# BoardForIV.net
KiCad netlist of a schematic drawn in Altium Designer
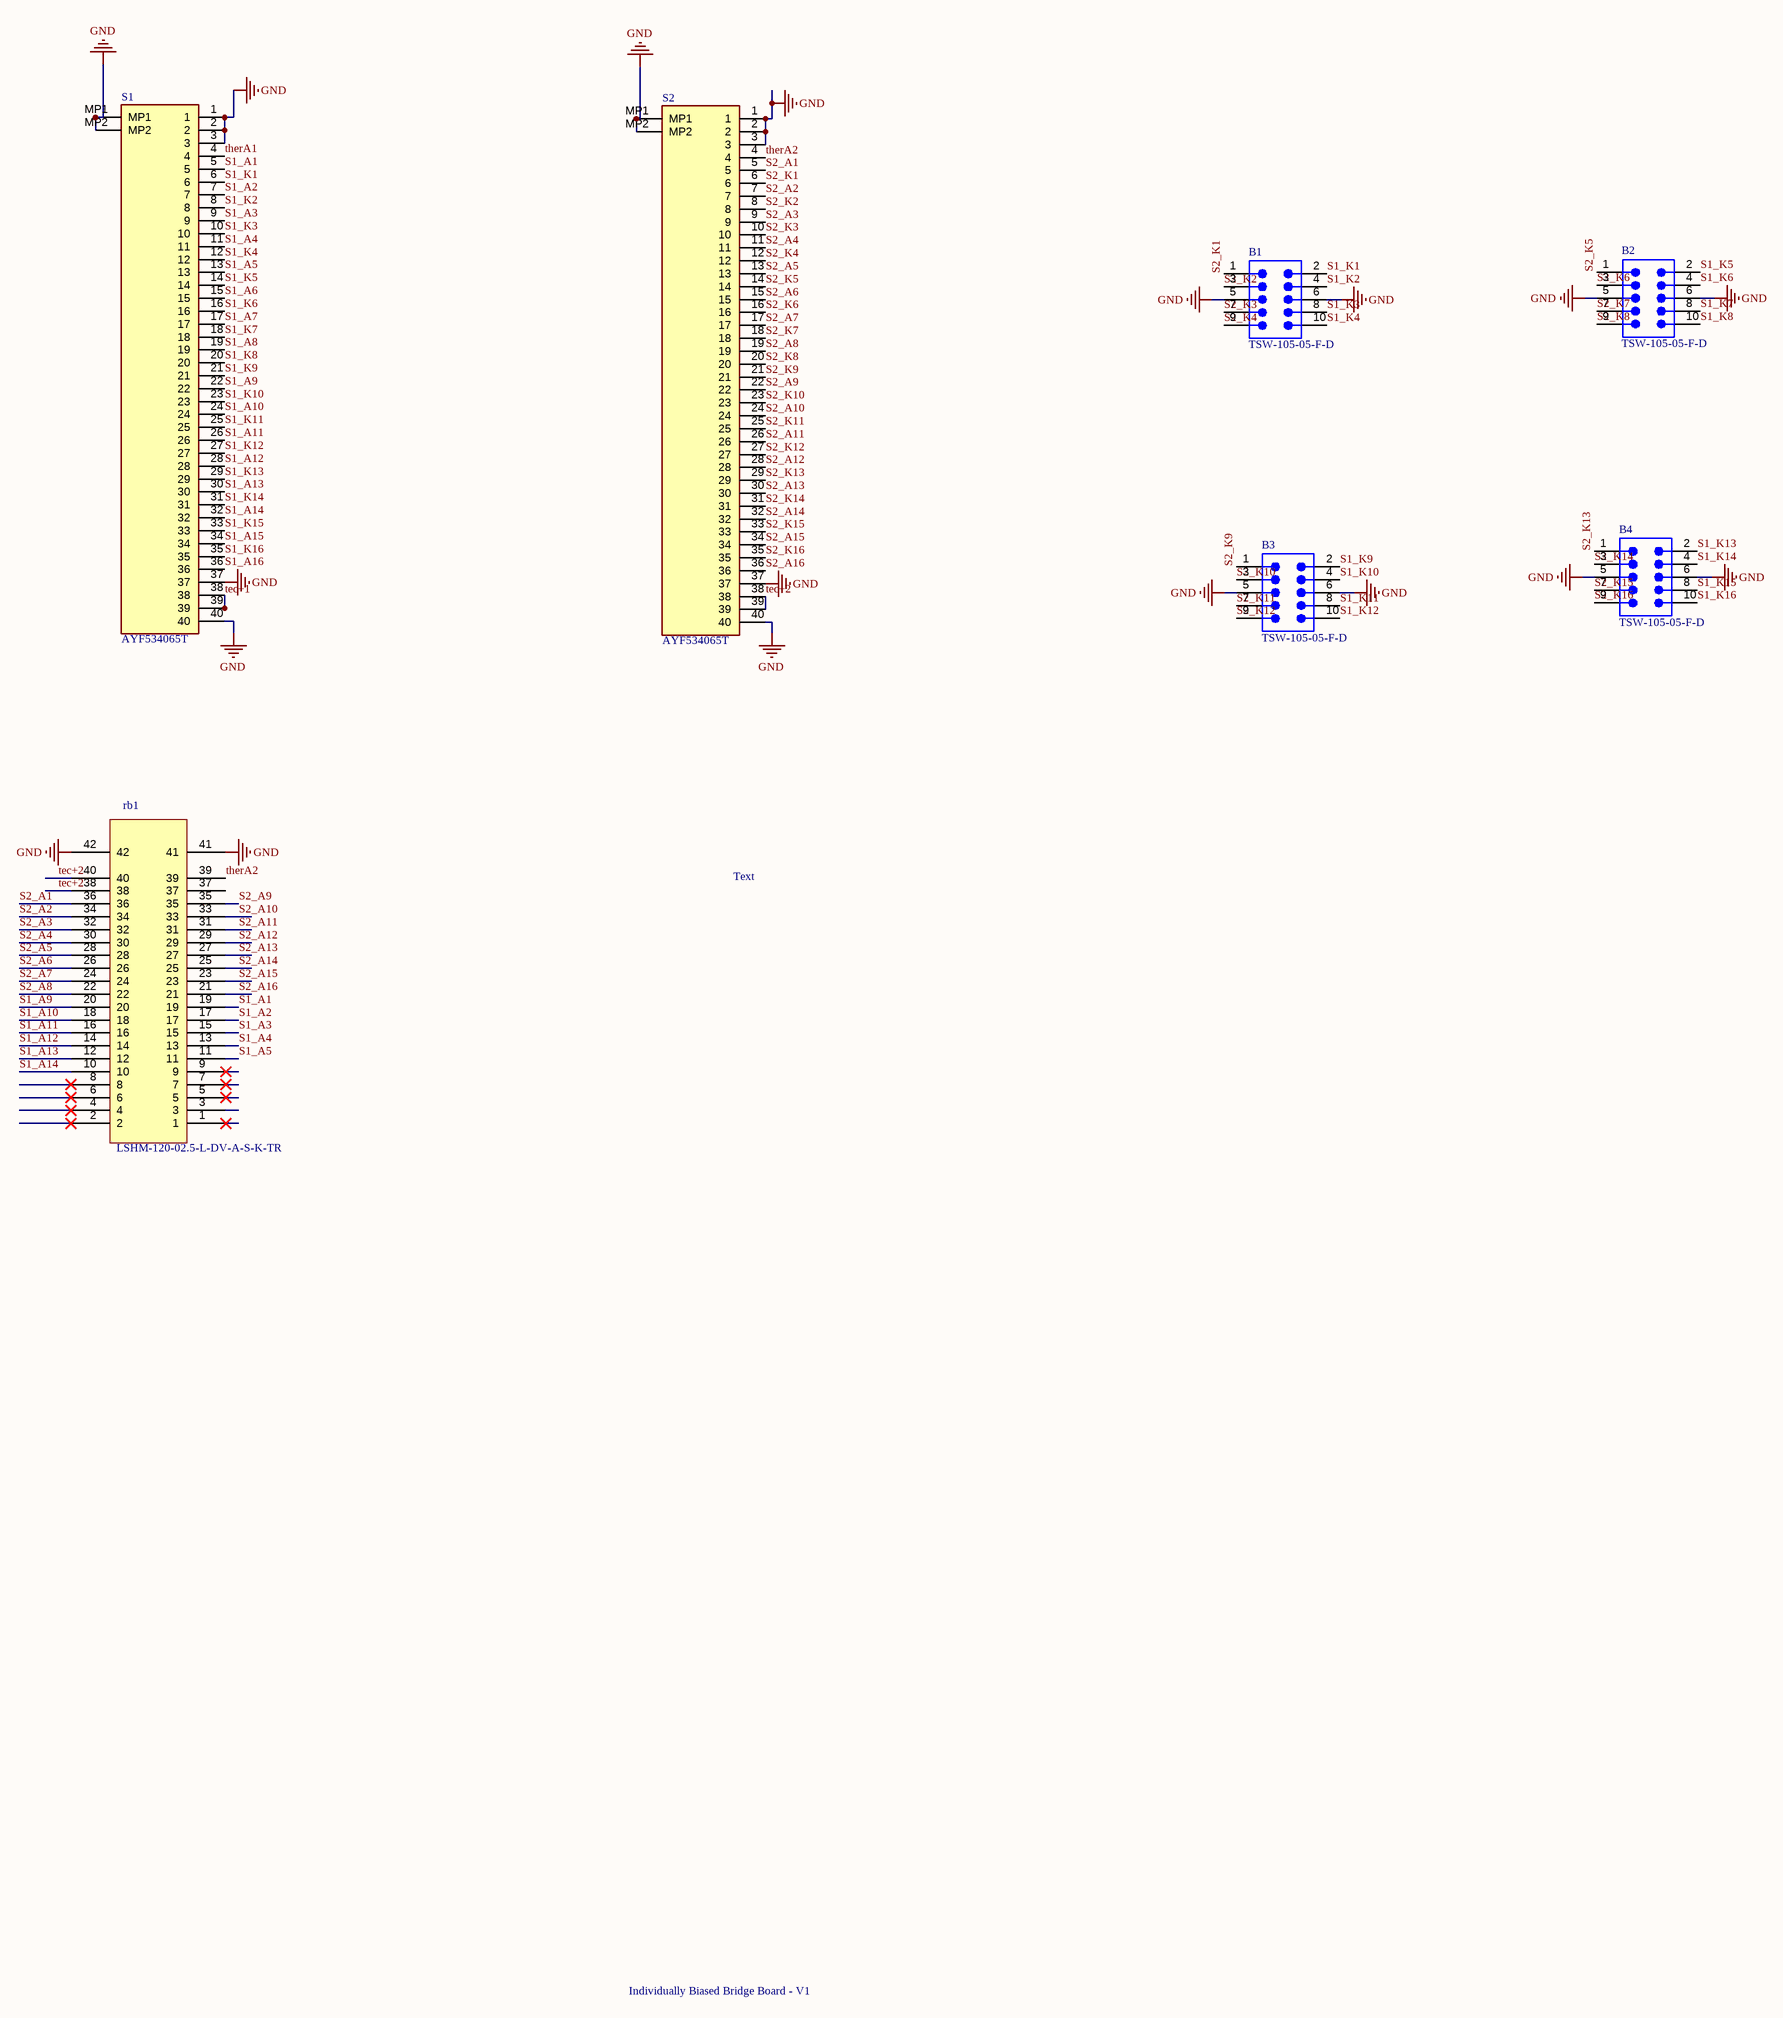
[diagram p0: BoardForIV.SchDoc]

(export (version "E")
  (design (tool "Eeschema 10.0.6"))
  (components
    (comp (ref "B1")
      (value "TSW-105-05-F-D")
      (footprint "SMTC-TSW-105-05-X-D")
      (description "0.025\" SQ Post Header, Through-hole, Vertical, -55 to 125 degC, 2.54 mm Pitch, 10-Pin, Male, RoHS")
      (fields (field (name "MANUFACTURER") "Samtec"))
      (libsource (lib "Altium Content Vault") (part "SMTC-TSW-105-X-X-D-X"))
    )
    (comp (ref "B2")
      (value "TSW-105-05-F-D")
      (footprint "SMTC-TSW-105-05-X-D")
      (description "0.025\" SQ Post Header, Through-hole, Vertical, -55 to 125 degC, 2.54 mm Pitch, 10-Pin, Male, RoHS")
      (fields (field (name "MANUFACTURER") "Samtec"))
      (libsource (lib "Altium Content Vault") (part "SMTC-TSW-105-X-X-D-X"))
    )
    (comp (ref "B3")
      (value "TSW-105-05-F-D")
      (footprint "SMTC-TSW-105-05-X-D")
      (description "0.025\" SQ Post Header, Through-hole, Vertical, -55 to 125 degC, 2.54 mm Pitch, 10-Pin, Male, RoHS")
      (fields (field (name "MANUFACTURER") "Samtec"))
      (libsource (lib "Altium Content Vault") (part "SMTC-TSW-105-X-X-D-X"))
    )
    (comp (ref "B4")
      (value "TSW-105-05-F-D")
      (footprint "SMTC-TSW-105-05-X-D")
      (description "0.025\" SQ Post Header, Through-hole, Vertical, -55 to 125 degC, 2.54 mm Pitch, 10-Pin, Male, RoHS")
      (fields (field (name "MANUFACTURER") "Samtec"))
      (libsource (lib "Altium Content Vault") (part "SMTC-TSW-105-X-X-D-X"))
    )
    (comp (ref "rb1")
      (value "LSHM-120-02.5-L-DV-A-S-K-TR")
      (footprint "SAMTEC_LSHM-120-02.5-L-DV-A-S-TR")
      (description "razor beam 40")
      (libsource (lib "JPL") (part "LSHM-120-02.5-L-DV-A-S-K-TR"))
    )
    (comp (ref "S1")
      (value "AYF534065T")
      (footprint "AYF534065T:AYF534065T")
      (libsource (lib "SiPM") (part "AYF534035"))
    )
    (comp (ref "S2")
      (value "AYF534065T")
      (footprint "AYF534065T:AYF534065T")
      (libsource (lib "Miscellaneous Devices") (part "AYF534035"))
    )
  )
  (nets
    (net (code "1") (name "/S1_A1") (class "Default")
      (node (ref "S1") (pin "5") (pinfunction "5_5") (pintype "passive"))
      (node (ref "rb1") (pin "19") (pinfunction "19_19") (pintype "passive"))
    )
    (net (code "2") (name "/S1_A2") (class "Default")
      (node (ref "S1") (pin "7") (pinfunction "7_7") (pintype "passive"))
      (node (ref "rb1") (pin "17") (pinfunction "17_17") (pintype "passive"))
    )
    (net (code "3") (name "/S1_A3") (class "Default")
      (node (ref "S1") (pin "9") (pinfunction "9_9") (pintype "passive"))
      (node (ref "rb1") (pin "15") (pinfunction "15_15") (pintype "passive"))
    )
    (net (code "4") (name "/S1_A4") (class "Default")
      (node (ref "S1") (pin "11") (pinfunction "11_11") (pintype "passive"))
      (node (ref "rb1") (pin "13") (pinfunction "13_13") (pintype "passive"))
    )
    (net (code "5") (name "/S1_A5") (class "Default")
      (node (ref "S1") (pin "13") (pinfunction "13_13") (pintype "passive"))
      (node (ref "rb1") (pin "11") (pinfunction "11_11") (pintype "passive"))
    )
    (net (code "6") (name "/S1_A6") (class "Default")
      (node (ref "S1") (pin "15") (pinfunction "15_15") (pintype "passive"))
    )
    (net (code "7") (name "/S1_A7") (class "Default")
      (node (ref "S1") (pin "17") (pinfunction "17_17") (pintype "passive"))
    )
    (net (code "8") (name "/S1_A8") (class "Default")
      (node (ref "S1") (pin "19") (pinfunction "19_19") (pintype "passive"))
    )
    (net (code "9") (name "/S1_A9") (class "Default")
      (node (ref "S1") (pin "22") (pinfunction "22_22") (pintype "passive"))
      (node (ref "rb1") (pin "20") (pinfunction "20_20") (pintype "passive"))
    )
    (net (code "10") (name "/S1_A10") (class "Default")
      (node (ref "S1") (pin "24") (pinfunction "24_24") (pintype "passive"))
      (node (ref "rb1") (pin "18") (pinfunction "18_18") (pintype "passive"))
    )
    (net (code "11") (name "/S1_A11") (class "Default")
      (node (ref "S1") (pin "26") (pinfunction "26_26") (pintype "passive"))
      (node (ref "rb1") (pin "16") (pinfunction "16_16") (pintype "passive"))
    )
    (net (code "12") (name "/S1_A12") (class "Default")
      (node (ref "S1") (pin "28") (pinfunction "28_28") (pintype "passive"))
      (node (ref "rb1") (pin "14") (pinfunction "14_14") (pintype "passive"))
    )
    (net (code "13") (name "/S1_A13") (class "Default")
      (node (ref "S1") (pin "30") (pinfunction "30_30") (pintype "passive"))
      (node (ref "rb1") (pin "12") (pinfunction "12_12") (pintype "passive"))
    )
    (net (code "14") (name "/S1_A14") (class "Default")
      (node (ref "S1") (pin "32") (pinfunction "32_32") (pintype "passive"))
      (node (ref "rb1") (pin "10") (pinfunction "10_10") (pintype "passive"))
    )
    (net (code "15") (name "/S1_A15") (class "Default")
      (node (ref "S1") (pin "34") (pinfunction "34_34") (pintype "passive"))
    )
    (net (code "16") (name "/S1_A16") (class "Default")
      (node (ref "S1") (pin "36") (pinfunction "36_36") (pintype "passive"))
    )
    (net (code "17") (name "/S1_K1") (class "Default")
      (node (ref "B1") (pin "2") (pinfunction "2_2") (pintype "passive"))
      (node (ref "S1") (pin "6") (pinfunction "6_6") (pintype "passive"))
    )
    (net (code "18") (name "/S1_K2") (class "Default")
      (node (ref "B1") (pin "4") (pinfunction "4_4") (pintype "passive"))
      (node (ref "S1") (pin "8") (pinfunction "8_8") (pintype "passive"))
    )
    (net (code "19") (name "/S1_K3") (class "Default")
      (node (ref "B1") (pin "8") (pinfunction "8_8") (pintype "passive"))
      (node (ref "S1") (pin "10") (pinfunction "10_10") (pintype "passive"))
    )
    (net (code "20") (name "/S1_K4") (class "Default")
      (node (ref "B1") (pin "10") (pinfunction "10_10") (pintype "passive"))
      (node (ref "S1") (pin "12") (pinfunction "12_12") (pintype "passive"))
    )
    (net (code "21") (name "/S1_K5") (class "Default")
      (node (ref "B2") (pin "2") (pinfunction "2_2") (pintype "passive"))
      (node (ref "S1") (pin "14") (pinfunction "14_14") (pintype "passive"))
    )
    (net (code "22") (name "/S1_K6") (class "Default")
      (node (ref "B2") (pin "4") (pinfunction "4_4") (pintype "passive"))
      (node (ref "S1") (pin "16") (pinfunction "16_16") (pintype "passive"))
    )
    (net (code "23") (name "/S1_K7") (class "Default")
      (node (ref "B2") (pin "8") (pinfunction "8_8") (pintype "passive"))
      (node (ref "S1") (pin "18") (pinfunction "18_18") (pintype "passive"))
    )
    (net (code "24") (name "/S1_K8") (class "Default")
      (node (ref "B2") (pin "10") (pinfunction "10_10") (pintype "passive"))
      (node (ref "S1") (pin "20") (pinfunction "20_20") (pintype "passive"))
    )
    (net (code "25") (name "/S1_K9") (class "Default")
      (node (ref "B3") (pin "2") (pinfunction "2_2") (pintype "passive"))
      (node (ref "S1") (pin "21") (pinfunction "21_21") (pintype "passive"))
    )
    (net (code "26") (name "/S1_K10") (class "Default")
      (node (ref "B3") (pin "4") (pinfunction "4_4") (pintype "passive"))
      (node (ref "S1") (pin "23") (pinfunction "23_23") (pintype "passive"))
    )
    (net (code "27") (name "/S1_K11") (class "Default")
      (node (ref "B3") (pin "8") (pinfunction "8_8") (pintype "passive"))
      (node (ref "S1") (pin "25") (pinfunction "25_25") (pintype "passive"))
    )
    (net (code "28") (name "/S1_K12") (class "Default")
      (node (ref "B3") (pin "10") (pinfunction "10_10") (pintype "passive"))
      (node (ref "S1") (pin "27") (pinfunction "27_27") (pintype "passive"))
    )
    (net (code "29") (name "/S1_K13") (class "Default")
      (node (ref "B4") (pin "2") (pinfunction "2_2") (pintype "passive"))
      (node (ref "S1") (pin "29") (pinfunction "29_29") (pintype "passive"))
    )
    (net (code "30") (name "/S1_K14") (class "Default")
      (node (ref "B4") (pin "4") (pinfunction "4_4") (pintype "passive"))
      (node (ref "S1") (pin "31") (pinfunction "31_31") (pintype "passive"))
    )
    (net (code "31") (name "/S1_K15") (class "Default")
      (node (ref "B4") (pin "8") (pinfunction "8_8") (pintype "passive"))
      (node (ref "S1") (pin "33") (pinfunction "33_33") (pintype "passive"))
    )
    (net (code "32") (name "/S1_K16") (class "Default")
      (node (ref "B4") (pin "10") (pinfunction "10_10") (pintype "passive"))
      (node (ref "S1") (pin "35") (pinfunction "35_35") (pintype "passive"))
    )
    (net (code "33") (name "/S2_A1") (class "Default")
      (node (ref "S2") (pin "5") (pinfunction "5_5") (pintype "passive"))
      (node (ref "rb1") (pin "36") (pinfunction "36_36") (pintype "passive"))
    )
    (net (code "34") (name "/S2_A2") (class "Default")
      (node (ref "S2") (pin "7") (pinfunction "7_7") (pintype "passive"))
      (node (ref "rb1") (pin "34") (pinfunction "34_34") (pintype "passive"))
    )
    (net (code "35") (name "/S2_A3") (class "Default")
      (node (ref "S2") (pin "9") (pinfunction "9_9") (pintype "passive"))
      (node (ref "rb1") (pin "32") (pinfunction "32_32") (pintype "passive"))
    )
    (net (code "36") (name "/S2_A4") (class "Default")
      (node (ref "S2") (pin "11") (pinfunction "11_11") (pintype "passive"))
      (node (ref "rb1") (pin "30") (pinfunction "30_30") (pintype "passive"))
    )
    (net (code "37") (name "/S2_A5") (class "Default")
      (node (ref "S2") (pin "13") (pinfunction "13_13") (pintype "passive"))
      (node (ref "rb1") (pin "28") (pinfunction "28_28") (pintype "passive"))
    )
    (net (code "38") (name "/S2_A6") (class "Default")
      (node (ref "S2") (pin "15") (pinfunction "15_15") (pintype "passive"))
      (node (ref "rb1") (pin "26") (pinfunction "26_26") (pintype "passive"))
    )
    (net (code "39") (name "/S2_A7") (class "Default")
      (node (ref "S2") (pin "17") (pinfunction "17_17") (pintype "passive"))
      (node (ref "rb1") (pin "24") (pinfunction "24_24") (pintype "passive"))
    )
    (net (code "40") (name "/S2_A8") (class "Default")
      (node (ref "S2") (pin "19") (pinfunction "19_19") (pintype "passive"))
      (node (ref "rb1") (pin "22") (pinfunction "22_22") (pintype "passive"))
    )
    (net (code "41") (name "/S2_A9") (class "Default")
      (node (ref "S2") (pin "22") (pinfunction "22_22") (pintype "passive"))
      (node (ref "rb1") (pin "35") (pinfunction "35_35") (pintype "passive"))
    )
    (net (code "42") (name "/S2_A10") (class "Default")
      (node (ref "S2") (pin "24") (pinfunction "24_24") (pintype "passive"))
      (node (ref "rb1") (pin "33") (pinfunction "33_33") (pintype "passive"))
    )
    (net (code "43") (name "/S2_A11") (class "Default")
      (node (ref "S2") (pin "26") (pinfunction "26_26") (pintype "passive"))
      (node (ref "rb1") (pin "31") (pinfunction "31_31") (pintype "passive"))
    )
    (net (code "44") (name "/S2_A12") (class "Default")
      (node (ref "S2") (pin "28") (pinfunction "28_28") (pintype "passive"))
      (node (ref "rb1") (pin "29") (pinfunction "29_29") (pintype "passive"))
    )
    (net (code "45") (name "/S2_A13") (class "Default")
      (node (ref "S2") (pin "30") (pinfunction "30_30") (pintype "passive"))
      (node (ref "rb1") (pin "27") (pinfunction "27_27") (pintype "passive"))
    )
    (net (code "46") (name "/S2_A14") (class "Default")
      (node (ref "S2") (pin "32") (pinfunction "32_32") (pintype "passive"))
      (node (ref "rb1") (pin "25") (pinfunction "25_25") (pintype "passive"))
    )
    (net (code "47") (name "/S2_A15") (class "Default")
      (node (ref "S2") (pin "34") (pinfunction "34_34") (pintype "passive"))
      (node (ref "rb1") (pin "23") (pinfunction "23_23") (pintype "passive"))
    )
    (net (code "48") (name "/S2_A16") (class "Default")
      (node (ref "S2") (pin "36") (pinfunction "36_36") (pintype "passive"))
      (node (ref "rb1") (pin "21") (pinfunction "21_21") (pintype "passive"))
    )
    (net (code "49") (name "/S2_K1") (class "Default")
      (node (ref "B1") (pin "1") (pinfunction "1_1") (pintype "passive"))
      (node (ref "S2") (pin "6") (pinfunction "6_6") (pintype "passive"))
    )
    (net (code "50") (name "/S2_K2") (class "Default")
      (node (ref "B1") (pin "3") (pinfunction "3_3") (pintype "passive"))
      (node (ref "S2") (pin "8") (pinfunction "8_8") (pintype "passive"))
    )
    (net (code "51") (name "/S2_K3") (class "Default")
      (node (ref "B1") (pin "7") (pinfunction "7_7") (pintype "passive"))
      (node (ref "S2") (pin "10") (pinfunction "10_10") (pintype "passive"))
    )
    (net (code "52") (name "/S2_K4") (class "Default")
      (node (ref "B1") (pin "9") (pinfunction "9_9") (pintype "passive"))
      (node (ref "S2") (pin "12") (pinfunction "12_12") (pintype "passive"))
    )
    (net (code "53") (name "/S2_K5") (class "Default")
      (node (ref "B2") (pin "1") (pinfunction "1_1") (pintype "passive"))
      (node (ref "S2") (pin "14") (pinfunction "14_14") (pintype "passive"))
    )
    (net (code "54") (name "/S2_K6") (class "Default")
      (node (ref "B2") (pin "3") (pinfunction "3_3") (pintype "passive"))
      (node (ref "S2") (pin "16") (pinfunction "16_16") (pintype "passive"))
    )
    (net (code "55") (name "/S2_K7") (class "Default")
      (node (ref "B2") (pin "7") (pinfunction "7_7") (pintype "passive"))
      (node (ref "S2") (pin "18") (pinfunction "18_18") (pintype "passive"))
    )
    (net (code "56") (name "/S2_K8") (class "Default")
      (node (ref "B2") (pin "9") (pinfunction "9_9") (pintype "passive"))
      (node (ref "S2") (pin "20") (pinfunction "20_20") (pintype "passive"))
    )
    (net (code "57") (name "/S2_K9") (class "Default")
      (node (ref "B3") (pin "1") (pinfunction "1_1") (pintype "passive"))
      (node (ref "S2") (pin "21") (pinfunction "21_21") (pintype "passive"))
    )
    (net (code "58") (name "/S2_K10") (class "Default")
      (node (ref "B3") (pin "3") (pinfunction "3_3") (pintype "passive"))
      (node (ref "S2") (pin "23") (pinfunction "23_23") (pintype "passive"))
    )
    (net (code "59") (name "/S2_K11") (class "Default")
      (node (ref "B3") (pin "7") (pinfunction "7_7") (pintype "passive"))
      (node (ref "S2") (pin "25") (pinfunction "25_25") (pintype "passive"))
    )
    (net (code "60") (name "/S2_K12") (class "Default")
      (node (ref "B3") (pin "9") (pinfunction "9_9") (pintype "passive"))
      (node (ref "S2") (pin "27") (pinfunction "27_27") (pintype "passive"))
    )
    (net (code "61") (name "/S2_K13") (class "Default")
      (node (ref "B4") (pin "1") (pinfunction "1_1") (pintype "passive"))
      (node (ref "S2") (pin "29") (pinfunction "29_29") (pintype "passive"))
    )
    (net (code "62") (name "/S2_K14") (class "Default")
      (node (ref "B4") (pin "3") (pinfunction "3_3") (pintype "passive"))
      (node (ref "S2") (pin "31") (pinfunction "31_31") (pintype "passive"))
    )
    (net (code "63") (name "/S2_K15") (class "Default")
      (node (ref "B4") (pin "7") (pinfunction "7_7") (pintype "passive"))
      (node (ref "S2") (pin "33") (pinfunction "33_33") (pintype "passive"))
    )
    (net (code "64") (name "/S2_K16") (class "Default")
      (node (ref "B4") (pin "9") (pinfunction "9_9") (pintype "passive"))
      (node (ref "S2") (pin "35") (pinfunction "35_35") (pintype "passive"))
    )
    (net (code "65") (name "/tec+1") (class "Default")
      (node (ref "S1") (pin "38") (pinfunction "38_38") (pintype "passive"))
      (node (ref "S1") (pin "39") (pinfunction "39_39") (pintype "passive"))
    )
    (net (code "66") (name "/tec+2") (class "Default")
      (node (ref "S2") (pin "38") (pinfunction "38_38") (pintype "passive"))
      (node (ref "S2") (pin "39") (pinfunction "39_39") (pintype "passive"))
      (node (ref "rb1") (pin "38") (pinfunction "38_38") (pintype "passive"))
      (node (ref "rb1") (pin "40") (pinfunction "40_40") (pintype "passive"))
    )
    (net (code "67") (name "/therA1") (class "Default")
      (node (ref "S1") (pin "4") (pinfunction "4_4") (pintype "passive"))
    )
    (net (code "68") (name "/therA2") (class "Default")
      (node (ref "S2") (pin "4") (pinfunction "4_4") (pintype "passive"))
      (node (ref "rb1") (pin "39") (pinfunction "39_39") (pintype "passive"))
    )
    (net (code "69") (name "GND") (class "Default")
      (node (ref "B1") (pin "5") (pinfunction "5_5") (pintype "passive"))
      (node (ref "B1") (pin "6") (pinfunction "6_6") (pintype "passive"))
      (node (ref "B2") (pin "5") (pinfunction "5_5") (pintype "passive"))
      (node (ref "B2") (pin "6") (pinfunction "6_6") (pintype "passive"))
      (node (ref "B3") (pin "5") (pinfunction "5_5") (pintype "passive"))
      (node (ref "B3") (pin "6") (pinfunction "6_6") (pintype "passive"))
      (node (ref "B4") (pin "5") (pinfunction "5_5") (pintype "passive"))
      (node (ref "B4") (pin "6") (pinfunction "6_6") (pintype "passive"))
      (node (ref "S1") (pin "1") (pinfunction "1_1") (pintype "passive"))
      (node (ref "S1") (pin "2") (pinfunction "2_2") (pintype "passive"))
      (node (ref "S1") (pin "3") (pinfunction "3_3") (pintype "passive"))
      (node (ref "S1") (pin "37") (pinfunction "37_37") (pintype "passive"))
      (node (ref "S1") (pin "40") (pinfunction "40_40") (pintype "passive"))
      (node (ref "S1") (pin "MP1") (pinfunction "MP1_MP1") (pintype "passive"))
      (node (ref "S1") (pin "MP2") (pinfunction "MP2_MP2") (pintype "passive"))
      (node (ref "S2") (pin "1") (pinfunction "1_1") (pintype "passive"))
      (node (ref "S2") (pin "2") (pinfunction "2_2") (pintype "passive"))
      (node (ref "S2") (pin "3") (pinfunction "3_3") (pintype "passive"))
      (node (ref "S2") (pin "37") (pinfunction "37_37") (pintype "passive"))
      (node (ref "S2") (pin "40") (pinfunction "40_40") (pintype "passive"))
      (node (ref "S2") (pin "MP1") (pinfunction "MP1_MP1") (pintype "passive"))
      (node (ref "S2") (pin "MP2") (pinfunction "MP2_MP2") (pintype "passive"))
      (node (ref "rb1") (pin "41") (pinfunction "41_41") (pintype "passive"))
      (node (ref "rb1") (pin "42") (pinfunction "42_42") (pintype "passive"))
    )
    (net (code "70") (name "unconnected-(rb1-Pad1)") (class "Default")
      (node (ref "rb1") (pin "1") (pinfunction "1_1") (pintype "passive+no_connect"))
    )
    (net (code "71") (name "unconnected-(rb1-Pad2)") (class "Default")
      (node (ref "rb1") (pin "2") (pinfunction "2_2") (pintype "passive+no_connect"))
    )
    (net (code "72") (name "unconnected-(rb1-Pad3)") (class "Default")
      (node (ref "rb1") (pin "3") (pinfunction "3_3") (pintype "passive"))
    )
    (net (code "73") (name "unconnected-(rb1-Pad4)") (class "Default")
      (node (ref "rb1") (pin "4") (pinfunction "4_4") (pintype "passive+no_connect"))
    )
    (net (code "74") (name "unconnected-(rb1-Pad5)") (class "Default")
      (node (ref "rb1") (pin "5") (pinfunction "5_5") (pintype "passive+no_connect"))
    )
    (net (code "75") (name "unconnected-(rb1-Pad6)") (class "Default")
      (node (ref "rb1") (pin "6") (pinfunction "6_6") (pintype "passive+no_connect"))
    )
    (net (code "76") (name "unconnected-(rb1-Pad7)") (class "Default")
      (node (ref "rb1") (pin "7") (pinfunction "7_7") (pintype "passive+no_connect"))
    )
    (net (code "77") (name "unconnected-(rb1-Pad8)") (class "Default")
      (node (ref "rb1") (pin "8") (pinfunction "8_8") (pintype "passive+no_connect"))
    )
    (net (code "78") (name "unconnected-(rb1-Pad9)") (class "Default")
      (node (ref "rb1") (pin "9") (pinfunction "9_9") (pintype "passive+no_connect"))
    )
    (net (code "79") (name "unconnected-(rb1-Pad37)") (class "Default")
      (node (ref "rb1") (pin "37") (pinfunction "37_37") (pintype "passive"))
    )
  )
)
